# 05_eMMC.net
KiCad netlist of a schematic drawn in Altium Designer
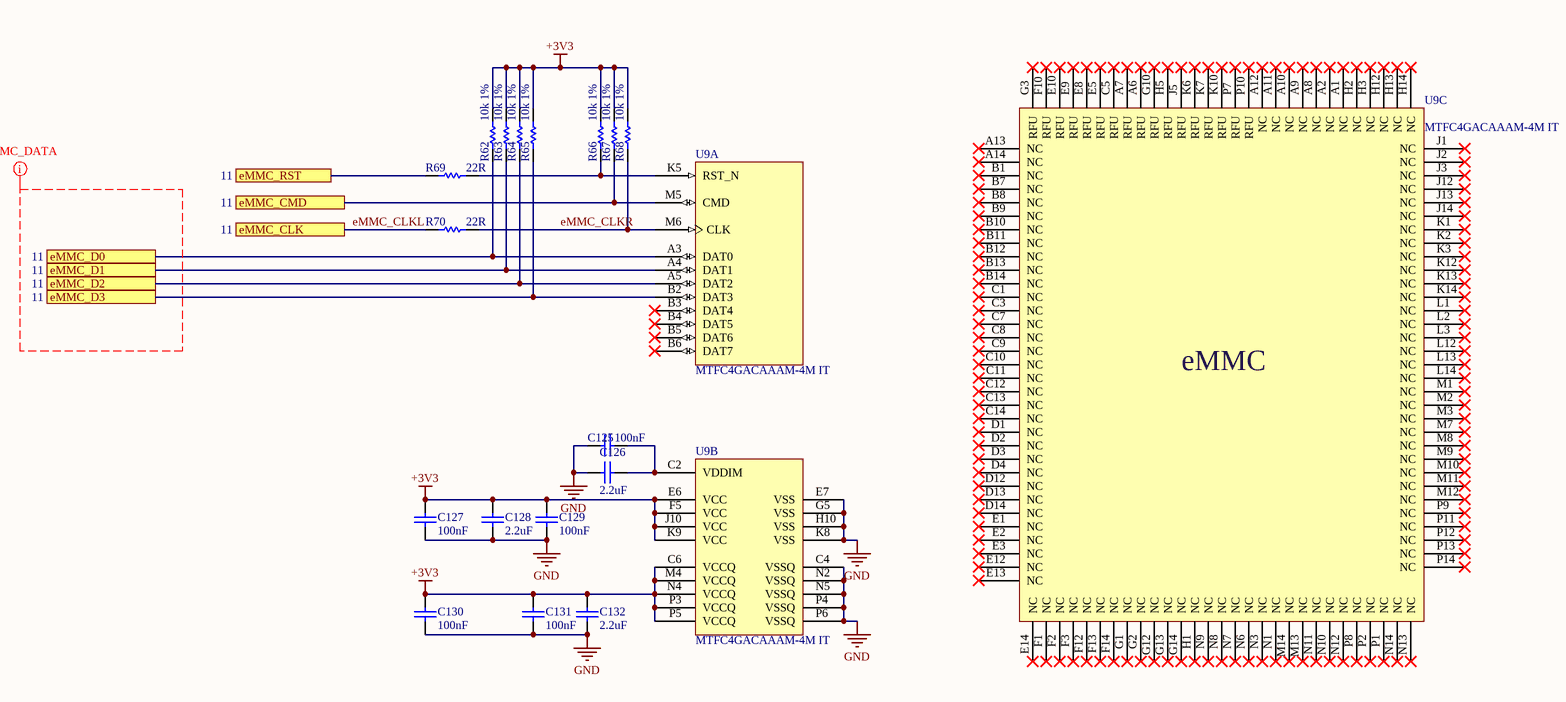
[diagram p0: 05. eMMC.SchDoc]

(export (version "E")
  (design (tool "Eeschema 10.0.6"))
  (components
    (comp (ref "C125")
      (value "100nF")
      (footprint "CAPC1005X60X30LL05T10")
      (description "Chip Capacitor, 0.1 uF, +/- 10%, 16 V, -55 to 125 degC, 0402 (1005 Metric), RoHS, Tape and Reel")
      (fields (field (name "VOLTAGE") "16V") (field (name "TOLERANCE") "10%"))
      (libsource (lib "AM3358_DEV_BOARD") (part "CAP-NP-2"))
    )
    (comp (ref "C126")
      (value "2.2uF")
      (footprint "CAPC1608X90X35ML10T15")
      (description "CAP 2.2uF 10V ±10% 0603 (1608 Metric) Thickness 0.6mm SMD")
      (fields (field (name "MANUFACTURER") "Murata") (field (name "PART NUMBER") "GRM188R71A225KE15D"))
      (libsource (lib "Altium Content Vault") (part "CAP"))
    )
    (comp (ref "C127")
      (value "100nF")
      (footprint "CAPC1005X60X30LL05T10")
      (description "Chip Capacitor, 0.1 uF, +/- 10%, 16 V, -55 to 125 degC, 0402 (1005 Metric), RoHS, Tape and Reel")
      (fields (field (name "VOLTAGE") "16V") (field (name "TOLERANCE") "10%"))
      (libsource (lib "AM3358_DEV_BOARD") (part "CAP-NP-2"))
    )
    (comp (ref "C128")
      (value "2.2uF")
      (footprint "CAPC1005X60X30LL05T10")
      (description "CAP 2.2uF 10V ±10% 0603 (1608 Metric) Thickness 0.6mm SMD")
      (fields (field (name "MANUFACTURER") "Murata") (field (name "PART NUMBER") "GRM188R71A225KE15D"))
      (libsource (lib "AM3358_DEV_BOARD") (part "CAP"))
    )
    (comp (ref "C129")
      (value "100nF")
      (footprint "CAPC1005X60X30LL05T10")
      (description "Chip Capacitor, 0.1 uF, +/- 10%, 16 V, -55 to 125 degC, 0402 (1005 Metric), RoHS, Tape and Reel")
      (fields (field (name "VOLTAGE") "16V") (field (name "TOLERANCE") "10%"))
      (libsource (lib "AM3358_DEV_BOARD") (part "CAP-NP-2"))
    )
    (comp (ref "C130")
      (value "100nF")
      (footprint "CAPC1005X60X30LL05T10")
      (description "Chip Capacitor, 0.1 uF, +/- 10%, 16 V, -55 to 125 degC, 0402 (1005 Metric), RoHS, Tape and Reel")
      (fields (field (name "VOLTAGE") "16V") (field (name "TOLERANCE") "10%"))
      (libsource (lib "AM3358_DEV_BOARD") (part "CAP-NP-2"))
    )
    (comp (ref "C131")
      (value "100nF")
      (footprint "CAPC1005X60X30LL05T10")
      (description "Chip Capacitor, 0.1 uF, +/- 10%, 16 V, -55 to 125 degC, 0402 (1005 Metric), RoHS, Tape and Reel")
      (fields (field (name "VOLTAGE") "16V") (field (name "TOLERANCE") "10%"))
      (libsource (lib "AM3358_DEV_BOARD") (part "CAP-NP-2"))
    )
    (comp (ref "C132")
      (value "2.2uF")
      (footprint "CAPC1608X90X35ML10T15")
      (description "CAP 2.2uF 10V ±10% 0603 (1608 Metric) Thickness 0.6mm SMD")
      (fields (field (name "MANUFACTURER") "Murata") (field (name "PART NUMBER") "GRM188R71A225KE15D"))
      (libsource (lib "Altium Content Vault") (part "CAP"))
    )
    (comp (ref "R62")
      (value "10k 1%")
      (footprint "RESC1005X40X25LL05T05")
      (description "10k 0.063W 1% 0402 (1005 Metric)  SMD")
      (fields (field (name "MANUFACTURER") "Vishay Dale") (field (name "PART NUMBER") "CRCW040210K0FKED"))
      (libsource (lib "AM3358_DEV_BOARD") (part "RES"))
    )
    (comp (ref "R63")
      (value "10k 1%")
      (footprint "RESC1005X40X25LL05T05")
      (description "10k 0.063W 1% 0402 (1005 Metric)  SMD")
      (fields (field (name "MANUFACTURER") "Vishay Dale") (field (name "PART NUMBER") "CRCW040210K0FKED"))
      (libsource (lib "AM3358_DEV_BOARD") (part "RES"))
    )
    (comp (ref "R64")
      (value "10k 1%")
      (footprint "RESC1005X40X25LL05T05")
      (description "10k 0.063W 1% 0402 (1005 Metric)  SMD")
      (fields (field (name "MANUFACTURER") "Vishay Dale") (field (name "PART NUMBER") "CRCW040210K0FKED"))
      (libsource (lib "AM3358_DEV_BOARD") (part "RES"))
    )
    (comp (ref "R65")
      (value "10k 1%")
      (footprint "RESC1005X40X25LL05T05")
      (description "10k 0.063W 1% 0402 (1005 Metric)  SMD")
      (fields (field (name "MANUFACTURER") "Vishay Dale") (field (name "PART NUMBER") "CRCW040210K0FKED"))
      (libsource (lib "AM3358_DEV_BOARD") (part "RES"))
    )
    (comp (ref "R66")
      (value "10k 1%")
      (footprint "RESC1005X40X25LL05T05")
      (description "10k 0.063W 1% 0402 (1005 Metric)  SMD")
      (fields (field (name "MANUFACTURER") "Vishay Dale") (field (name "PART NUMBER") "CRCW040210K0FKED"))
      (libsource (lib "AM3358_DEV_BOARD") (part "RES"))
    )
    (comp (ref "R67")
      (value "10k 1%")
      (footprint "RESC1005X40X25LL05T05")
      (description "10k 0.063W 1% 0402 (1005 Metric)  SMD")
      (fields (field (name "MANUFACTURER") "Vishay Dale") (field (name "PART NUMBER") "CRCW040210K0FKED"))
      (libsource (lib "AM3358_DEV_BOARD") (part "RES"))
    )
    (comp (ref "R68")
      (value "10k 1%")
      (footprint "RESC1005X40X25LL05T05")
      (description "10k 0.063W 1% 0402 (1005 Metric)  SMD")
      (fields (field (name "MANUFACTURER") "Vishay Dale") (field (name "PART NUMBER") "CRCW040210K0FKED"))
      (libsource (lib "AM3358_DEV_BOARD") (part "RES"))
    )
    (comp (ref "R69")
      (value "22R")
      (footprint "RESC1005X40X25LL05T05")
      (description "Chip Resistor, 22 Ohm, +/- 1%, 0.1 W, -55 to 155 degC, 0402 (1005 Metric), RoHS, Tape and Reel")
      (fields (field (name "PARTNUMBER") "ERJ-2RKF22R0X") (field (name "TOLERANCE") "1%"))
      (libsource (lib "AM3358_DEV_BOARD") (part "RES-2"))
    )
    (comp (ref "R70")
      (value "22R")
      (footprint "RESC1005X40X25LL05T05")
      (description "Chip Resistor, 22 Ohm, +/- 1%, 0.1 W, -55 to 155 degC, 0402 (1005 Metric), RoHS, Tape and Reel")
      (fields (field (name "PARTNUMBER") "ERJ-2RKF22R0X") (field (name "TOLERANCE") "1%"))
      (libsource (lib "AM3358_DEV_BOARD") (part "RES-2"))
    )
    (comp (ref "U9")
      (value "MTFC4GACAAAM-4M IT")
      (footprint "VFBGA-153")
      (description "e·MMC Memory, 4 Gb, 2.7 to 3.6 V, -40 to 85 degC, 153-Ball VFBGA, RoHS")
      (fields (field (name "MANUFACTURER") "Micron"))
      (libsource (lib "AM3358_DEV_BOARD") (part "CMP-2000-05234-1"))
    )
  )
  (nets
    (net (code "1") (name "+3V3") (class "Default")
      (node (ref "C127") (pin "2") (pinfunction "2_2") (pintype "passive"))
      (node (ref "C128") (pin "2") (pinfunction "2_2") (pintype "passive"))
      (node (ref "C129") (pin "2") (pinfunction "2_2") (pintype "passive"))
      (node (ref "C130") (pin "2") (pinfunction "2_2") (pintype "passive"))
      (node (ref "C131") (pin "2") (pinfunction "2_2") (pintype "passive"))
      (node (ref "C132") (pin "2") (pinfunction "2_2") (pintype "passive"))
      (node (ref "R62") (pin "2") (pinfunction "2_2") (pintype "passive"))
      (node (ref "R63") (pin "2") (pinfunction "2_2") (pintype "passive"))
      (node (ref "R64") (pin "2") (pinfunction "2_2") (pintype "passive"))
      (node (ref "R65") (pin "2") (pinfunction "2_2") (pintype "passive"))
      (node (ref "R66") (pin "2") (pinfunction "2_2") (pintype "passive"))
      (node (ref "R67") (pin "2") (pinfunction "2_2") (pintype "passive"))
      (node (ref "R68") (pin "2") (pinfunction "2_2") (pintype "passive"))
      (node (ref "U9") (pin "C6") (pinfunction "VCCQ_C6") (pintype "power_in"))
      (node (ref "U9") (pin "E6") (pinfunction "VCC_E6") (pintype "power_in"))
      (node (ref "U9") (pin "F5") (pinfunction "VCC_F5") (pintype "power_in"))
      (node (ref "U9") (pin "J10") (pinfunction "VCC_J10") (pintype "power_in"))
      (node (ref "U9") (pin "K9") (pinfunction "VCC_K9") (pintype "power_in"))
      (node (ref "U9") (pin "M4") (pinfunction "VCCQ_M4") (pintype "power_in"))
      (node (ref "U9") (pin "N4") (pinfunction "VCCQ_N4") (pintype "power_in"))
      (node (ref "U9") (pin "P3") (pinfunction "VCCQ_P3") (pintype "power_in"))
      (node (ref "U9") (pin "P5") (pinfunction "VCCQ_P5") (pintype "power_in"))
    )
    (net (code "2") (name "/eMMC_CLKL") (class "Default")
      (node (ref "R70") (pin "1") (pinfunction "1_1") (pintype "passive"))
    )
    (net (code "3") (name "/eMMC_CLKR") (class "Default")
      (node (ref "R68") (pin "1") (pinfunction "1_1") (pintype "passive"))
      (node (ref "R70") (pin "2") (pinfunction "2_2") (pintype "passive"))
      (node (ref "U9") (pin "M6") (pinfunction "CLK_M6") (pintype "input"))
    )
    (net (code "4") (name "/eMMC_CMD") (class "Default")
      (node (ref "R67") (pin "1") (pinfunction "1_1") (pintype "passive"))
      (node (ref "U9") (pin "M5") (pinfunction "CMD_M5") (pintype "bidirectional"))
    )
    (net (code "5") (name "/eMMC_D0") (class "Default")
      (node (ref "R62") (pin "1") (pinfunction "1_1") (pintype "passive"))
      (node (ref "U9") (pin "A3") (pinfunction "DAT0_A3") (pintype "bidirectional"))
    )
    (net (code "6") (name "/eMMC_D1") (class "Default")
      (node (ref "R63") (pin "1") (pinfunction "1_1") (pintype "passive"))
      (node (ref "U9") (pin "A4") (pinfunction "DAT1_A4") (pintype "bidirectional"))
    )
    (net (code "7") (name "/eMMC_D2") (class "Default")
      (node (ref "R64") (pin "1") (pinfunction "1_1") (pintype "passive"))
      (node (ref "U9") (pin "A5") (pinfunction "DAT2_A5") (pintype "bidirectional"))
    )
    (net (code "8") (name "/eMMC_D3") (class "Default")
      (node (ref "R65") (pin "1") (pinfunction "1_1") (pintype "passive"))
      (node (ref "U9") (pin "B2") (pinfunction "DAT3_B2") (pintype "bidirectional"))
    )
    (net (code "9") (name "/eMMC_RST") (class "Default")
      (node (ref "R69") (pin "1") (pinfunction "1_1") (pintype "passive"))
    )
    (net (code "10") (name "GND") (class "Default")
      (node (ref "C125") (pin "2") (pinfunction "2_2") (pintype "passive"))
      (node (ref "C126") (pin "2") (pinfunction "2_2") (pintype "passive"))
      (node (ref "C127") (pin "1") (pinfunction "1_1") (pintype "passive"))
      (node (ref "C128") (pin "1") (pinfunction "1_1") (pintype "passive"))
      (node (ref "C129") (pin "1") (pinfunction "1_1") (pintype "passive"))
      (node (ref "C130") (pin "1") (pinfunction "1_1") (pintype "passive"))
      (node (ref "C131") (pin "1") (pinfunction "1_1") (pintype "passive"))
      (node (ref "C132") (pin "1") (pinfunction "1_1") (pintype "passive"))
      (node (ref "U9") (pin "C4") (pinfunction "VSSQ_C4") (pintype "power_in"))
      (node (ref "U9") (pin "E7") (pinfunction "VSS_E7") (pintype "power_in"))
      (node (ref "U9") (pin "G5") (pinfunction "VSS_G5") (pintype "power_in"))
      (node (ref "U9") (pin "H10") (pinfunction "VSS_H10") (pintype "power_in"))
      (node (ref "U9") (pin "K8") (pinfunction "VSS_K8") (pintype "power_in"))
      (node (ref "U9") (pin "N2") (pinfunction "VSSQ_N2") (pintype "power_in"))
      (node (ref "U9") (pin "N5") (pinfunction "VSSQ_N5") (pintype "power_in"))
      (node (ref "U9") (pin "P4") (pinfunction "VSSQ_P4") (pintype "power_in"))
      (node (ref "U9") (pin "P6") (pinfunction "VSSQ_P6") (pintype "power_in"))
    )
    (net (code "11") (name "Net-(U9A-RST_N)") (class "Default")
      (node (ref "R66") (pin "1") (pinfunction "1_1") (pintype "passive"))
      (node (ref "R69") (pin "2") (pinfunction "2_2") (pintype "passive"))
      (node (ref "U9") (pin "K5") (pinfunction "RST_N_K5") (pintype "input"))
    )
    (net (code "12") (name "Net-(U9B-VDDIM)") (class "Default")
      (node (ref "C125") (pin "1") (pinfunction "1_1") (pintype "passive"))
      (node (ref "C126") (pin "1") (pinfunction "1_1") (pintype "passive"))
      (node (ref "U9") (pin "C2") (pinfunction "VDDIM_C2") (pintype "power_in"))
    )
    (net (code "13") (name "unconnected-(U9A-DAT4-PadB3)") (class "Default")
      (node (ref "U9") (pin "B3") (pinfunction "DAT4_B3") (pintype "bidirectional+no_connect"))
    )
    (net (code "14") (name "unconnected-(U9A-DAT5-PadB4)") (class "Default")
      (node (ref "U9") (pin "B4") (pinfunction "DAT5_B4") (pintype "bidirectional+no_connect"))
    )
    (net (code "15") (name "unconnected-(U9A-DAT6-PadB5)") (class "Default")
      (node (ref "U9") (pin "B5") (pinfunction "DAT6_B5") (pintype "bidirectional+no_connect"))
    )
    (net (code "16") (name "unconnected-(U9A-DAT7-PadB6)") (class "Default")
      (node (ref "U9") (pin "B6") (pinfunction "DAT7_B6") (pintype "bidirectional+no_connect"))
    )
    (net (code "17") (name "unconnected-(U9C-NC-PadA1)") (class "Default")
      (node (ref "U9") (pin "A1") (pinfunction "NC_A1") (pintype "passive+no_connect"))
    )
    (net (code "18") (name "unconnected-(U9C-NC-PadA2)") (class "Default")
      (node (ref "U9") (pin "A2") (pinfunction "NC_A2") (pintype "passive+no_connect"))
    )
    (net (code "19") (name "unconnected-(U9C-NC-PadA8)") (class "Default")
      (node (ref "U9") (pin "A8") (pinfunction "NC_A8") (pintype "passive+no_connect"))
    )
    (net (code "20") (name "unconnected-(U9C-NC-PadA9)") (class "Default")
      (node (ref "U9") (pin "A9") (pinfunction "NC_A9") (pintype "passive+no_connect"))
    )
    (net (code "21") (name "unconnected-(U9C-NC-PadA10)") (class "Default")
      (node (ref "U9") (pin "A10") (pinfunction "NC_A10") (pintype "passive+no_connect"))
    )
    (net (code "22") (name "unconnected-(U9C-NC-PadA11)") (class "Default")
      (node (ref "U9") (pin "A11") (pinfunction "NC_A11") (pintype "passive+no_connect"))
    )
    (net (code "23") (name "unconnected-(U9C-NC-PadA12)") (class "Default")
      (node (ref "U9") (pin "A12") (pinfunction "NC_A12") (pintype "passive+no_connect"))
    )
    (net (code "24") (name "unconnected-(U9C-NC-PadA13)") (class "Default")
      (node (ref "U9") (pin "A13") (pinfunction "NC_A13") (pintype "passive+no_connect"))
    )
    (net (code "25") (name "unconnected-(U9C-NC-PadA14)") (class "Default")
      (node (ref "U9") (pin "A14") (pinfunction "NC_A14") (pintype "passive+no_connect"))
    )
    (net (code "26") (name "unconnected-(U9C-NC-PadB1)") (class "Default")
      (node (ref "U9") (pin "B1") (pinfunction "NC_B1") (pintype "passive+no_connect"))
    )
    (net (code "27") (name "unconnected-(U9C-NC-PadB7)") (class "Default")
      (node (ref "U9") (pin "B7") (pinfunction "NC_B7") (pintype "passive+no_connect"))
    )
    (net (code "28") (name "unconnected-(U9C-NC-PadB8)") (class "Default")
      (node (ref "U9") (pin "B8") (pinfunction "NC_B8") (pintype "passive+no_connect"))
    )
    (net (code "29") (name "unconnected-(U9C-NC-PadB9)") (class "Default")
      (node (ref "U9") (pin "B9") (pinfunction "NC_B9") (pintype "passive+no_connect"))
    )
    (net (code "30") (name "unconnected-(U9C-NC-PadB10)") (class "Default")
      (node (ref "U9") (pin "B10") (pinfunction "NC_B10") (pintype "passive+no_connect"))
    )
    (net (code "31") (name "unconnected-(U9C-NC-PadB11)") (class "Default")
      (node (ref "U9") (pin "B11") (pinfunction "NC_B11") (pintype "passive+no_connect"))
    )
    (net (code "32") (name "unconnected-(U9C-NC-PadB12)") (class "Default")
      (node (ref "U9") (pin "B12") (pinfunction "NC_B12") (pintype "passive+no_connect"))
    )
    (net (code "33") (name "unconnected-(U9C-NC-PadB13)") (class "Default")
      (node (ref "U9") (pin "B13") (pinfunction "NC_B13") (pintype "passive+no_connect"))
    )
    (net (code "34") (name "unconnected-(U9C-NC-PadB14)") (class "Default")
      (node (ref "U9") (pin "B14") (pinfunction "NC_B14") (pintype "passive+no_connect"))
    )
    (net (code "35") (name "unconnected-(U9C-NC-PadC1)") (class "Default")
      (node (ref "U9") (pin "C1") (pinfunction "NC_C1") (pintype "passive+no_connect"))
    )
    (net (code "36") (name "unconnected-(U9C-NC-PadC3)") (class "Default")
      (node (ref "U9") (pin "C3") (pinfunction "NC_C3") (pintype "passive+no_connect"))
    )
    (net (code "37") (name "unconnected-(U9C-NC-PadC7)") (class "Default")
      (node (ref "U9") (pin "C7") (pinfunction "NC_C7") (pintype "passive+no_connect"))
    )
    (net (code "38") (name "unconnected-(U9C-NC-PadC8)") (class "Default")
      (node (ref "U9") (pin "C8") (pinfunction "NC_C8") (pintype "passive+no_connect"))
    )
    (net (code "39") (name "unconnected-(U9C-NC-PadC9)") (class "Default")
      (node (ref "U9") (pin "C9") (pinfunction "NC_C9") (pintype "passive+no_connect"))
    )
    (net (code "40") (name "unconnected-(U9C-NC-PadC10)") (class "Default")
      (node (ref "U9") (pin "C10") (pinfunction "NC_C10") (pintype "passive+no_connect"))
    )
    (net (code "41") (name "unconnected-(U9C-NC-PadC11)") (class "Default")
      (node (ref "U9") (pin "C11") (pinfunction "NC_C11") (pintype "passive+no_connect"))
    )
    (net (code "42") (name "unconnected-(U9C-NC-PadC12)") (class "Default")
      (node (ref "U9") (pin "C12") (pinfunction "NC_C12") (pintype "passive+no_connect"))
    )
    (net (code "43") (name "unconnected-(U9C-NC-PadC13)") (class "Default")
      (node (ref "U9") (pin "C13") (pinfunction "NC_C13") (pintype "passive+no_connect"))
    )
    (net (code "44") (name "unconnected-(U9C-NC-PadC14)") (class "Default")
      (node (ref "U9") (pin "C14") (pinfunction "NC_C14") (pintype "passive+no_connect"))
    )
    (net (code "45") (name "unconnected-(U9C-NC-PadD1)") (class "Default")
      (node (ref "U9") (pin "D1") (pinfunction "NC_D1") (pintype "passive+no_connect"))
    )
    (net (code "46") (name "unconnected-(U9C-NC-PadD2)") (class "Default")
      (node (ref "U9") (pin "D2") (pinfunction "NC_D2") (pintype "passive+no_connect"))
    )
    (net (code "47") (name "unconnected-(U9C-NC-PadD3)") (class "Default")
      (node (ref "U9") (pin "D3") (pinfunction "NC_D3") (pintype "passive+no_connect"))
    )
    (net (code "48") (name "unconnected-(U9C-NC-PadD4)") (class "Default")
      (node (ref "U9") (pin "D4") (pinfunction "NC_D4") (pintype "passive+no_connect"))
    )
    (net (code "49") (name "unconnected-(U9C-NC-PadD12)") (class "Default")
      (node (ref "U9") (pin "D12") (pinfunction "NC_D12") (pintype "passive+no_connect"))
    )
    (net (code "50") (name "unconnected-(U9C-NC-PadD13)") (class "Default")
      (node (ref "U9") (pin "D13") (pinfunction "NC_D13") (pintype "passive+no_connect"))
    )
    (net (code "51") (name "unconnected-(U9C-NC-PadD14)") (class "Default")
      (node (ref "U9") (pin "D14") (pinfunction "NC_D14") (pintype "passive+no_connect"))
    )
    (net (code "52") (name "unconnected-(U9C-NC-PadE1)") (class "Default")
      (node (ref "U9") (pin "E1") (pinfunction "NC_E1") (pintype "passive+no_connect"))
    )
    (net (code "53") (name "unconnected-(U9C-NC-PadE2)") (class "Default")
      (node (ref "U9") (pin "E2") (pinfunction "NC_E2") (pintype "passive+no_connect"))
    )
    (net (code "54") (name "unconnected-(U9C-NC-PadE3)") (class "Default")
      (node (ref "U9") (pin "E3") (pinfunction "NC_E3") (pintype "passive+no_connect"))
    )
    (net (code "55") (name "unconnected-(U9C-NC-PadE12)") (class "Default")
      (node (ref "U9") (pin "E12") (pinfunction "NC_E12") (pintype "passive+no_connect"))
    )
    (net (code "56") (name "unconnected-(U9C-NC-PadE13)") (class "Default")
      (node (ref "U9") (pin "E13") (pinfunction "NC_E13") (pintype "passive+no_connect"))
    )
    (net (code "57") (name "unconnected-(U9C-NC-PadE14)") (class "Default")
      (node (ref "U9") (pin "E14") (pinfunction "NC_E14") (pintype "passive+no_connect"))
    )
    (net (code "58") (name "unconnected-(U9C-NC-PadF1)") (class "Default")
      (node (ref "U9") (pin "F1") (pinfunction "NC_F1") (pintype "passive+no_connect"))
    )
    (net (code "59") (name "unconnected-(U9C-NC-PadF2)") (class "Default")
      (node (ref "U9") (pin "F2") (pinfunction "NC_F2") (pintype "passive+no_connect"))
    )
    (net (code "60") (name "unconnected-(U9C-NC-PadF3)") (class "Default")
      (node (ref "U9") (pin "F3") (pinfunction "NC_F3") (pintype "passive+no_connect"))
    )
    (net (code "61") (name "unconnected-(U9C-NC-PadF12)") (class "Default")
      (node (ref "U9") (pin "F12") (pinfunction "NC_F12") (pintype "passive+no_connect"))
    )
    (net (code "62") (name "unconnected-(U9C-NC-PadF13)") (class "Default")
      (node (ref "U9") (pin "F13") (pinfunction "NC_F13") (pintype "passive+no_connect"))
    )
    (net (code "63") (name "unconnected-(U9C-NC-PadF14)") (class "Default")
      (node (ref "U9") (pin "F14") (pinfunction "NC_F14") (pintype "passive+no_connect"))
    )
    (net (code "64") (name "unconnected-(U9C-NC-PadG1)") (class "Default")
      (node (ref "U9") (pin "G1") (pinfunction "NC_G1") (pintype "passive+no_connect"))
    )
    (net (code "65") (name "unconnected-(U9C-NC-PadG2)") (class "Default")
      (node (ref "U9") (pin "G2") (pinfunction "NC_G2") (pintype "passive+no_connect"))
    )
    (net (code "66") (name "unconnected-(U9C-NC-PadG12)") (class "Default")
      (node (ref "U9") (pin "G12") (pinfunction "NC_G12") (pintype "passive+no_connect"))
    )
    (net (code "67") (name "unconnected-(U9C-NC-PadG13)") (class "Default")
      (node (ref "U9") (pin "G13") (pinfunction "NC_G13") (pintype "passive+no_connect"))
    )
    (net (code "68") (name "unconnected-(U9C-NC-PadG14)") (class "Default")
      (node (ref "U9") (pin "G14") (pinfunction "NC_G14") (pintype "passive+no_connect"))
    )
    (net (code "69") (name "unconnected-(U9C-NC-PadH1)") (class "Default")
      (node (ref "U9") (pin "H1") (pinfunction "NC_H1") (pintype "passive+no_connect"))
    )
    (net (code "70") (name "unconnected-(U9C-NC-PadH2)") (class "Default")
      (node (ref "U9") (pin "H2") (pinfunction "NC_H2") (pintype "passive+no_connect"))
    )
    (net (code "71") (name "unconnected-(U9C-NC-PadH3)") (class "Default")
      (node (ref "U9") (pin "H3") (pinfunction "NC_H3") (pintype "passive+no_connect"))
    )
    (net (code "72") (name "unconnected-(U9C-NC-PadH12)") (class "Default")
      (node (ref "U9") (pin "H12") (pinfunction "NC_H12") (pintype "passive+no_connect"))
    )
    (net (code "73") (name "unconnected-(U9C-NC-PadH13)") (class "Default")
      (node (ref "U9") (pin "H13") (pinfunction "NC_H13") (pintype "passive+no_connect"))
    )
    (net (code "74") (name "unconnected-(U9C-NC-PadH14)") (class "Default")
      (node (ref "U9") (pin "H14") (pinfunction "NC_H14") (pintype "passive+no_connect"))
    )
    (net (code "75") (name "unconnected-(U9C-NC-PadJ1)") (class "Default")
      (node (ref "U9") (pin "J1") (pinfunction "NC_J1") (pintype "passive+no_connect"))
    )
    (net (code "76") (name "unconnected-(U9C-NC-PadJ2)") (class "Default")
      (node (ref "U9") (pin "J2") (pinfunction "NC_J2") (pintype "passive+no_connect"))
    )
    (net (code "77") (name "unconnected-(U9C-NC-PadJ3)") (class "Default")
      (node (ref "U9") (pin "J3") (pinfunction "NC_J3") (pintype "passive+no_connect"))
    )
    (net (code "78") (name "unconnected-(U9C-NC-PadJ12)") (class "Default")
      (node (ref "U9") (pin "J12") (pinfunction "NC_J12") (pintype "passive+no_connect"))
    )
    (net (code "79") (name "unconnected-(U9C-NC-PadJ13)") (class "Default")
      (node (ref "U9") (pin "J13") (pinfunction "NC_J13") (pintype "passive+no_connect"))
    )
    (net (code "80") (name "unconnected-(U9C-NC-PadJ14)") (class "Default")
      (node (ref "U9") (pin "J14") (pinfunction "NC_J14") (pintype "passive+no_connect"))
    )
    (net (code "81") (name "unconnected-(U9C-NC-PadK1)") (class "Default")
      (node (ref "U9") (pin "K1") (pinfunction "NC_K1") (pintype "passive+no_connect"))
    )
    (net (code "82") (name "unconnected-(U9C-NC-PadK2)") (class "Default")
      (node (ref "U9") (pin "K2") (pinfunction "NC_K2") (pintype "passive+no_connect"))
    )
    (net (code "83") (name "unconnected-(U9C-NC-PadK3)") (class "Default")
      (node (ref "U9") (pin "K3") (pinfunction "NC_K3") (pintype "passive+no_connect"))
    )
    (net (code "84") (name "unconnected-(U9C-NC-PadK12)") (class "Default")
      (node (ref "U9") (pin "K12") (pinfunction "NC_K12") (pintype "passive+no_connect"))
    )
    (net (code "85") (name "unconnected-(U9C-NC-PadK13)") (class "Default")
      (node (ref "U9") (pin "K13") (pinfunction "NC_K13") (pintype "passive+no_connect"))
    )
    (net (code "86") (name "unconnected-(U9C-NC-PadK14)") (class "Default")
      (node (ref "U9") (pin "K14") (pinfunction "NC_K14") (pintype "passive+no_connect"))
    )
    (net (code "87") (name "unconnected-(U9C-NC-PadL1)") (class "Default")
      (node (ref "U9") (pin "L1") (pinfunction "NC_L1") (pintype "passive+no_connect"))
    )
    (net (code "88") (name "unconnected-(U9C-NC-PadL2)") (class "Default")
      (node (ref "U9") (pin "L2") (pinfunction "NC_L2") (pintype "passive+no_connect"))
    )
    (net (code "89") (name "unconnected-(U9C-NC-PadL3)") (class "Default")
      (node (ref "U9") (pin "L3") (pinfunction "NC_L3") (pintype "passive+no_connect"))
    )
    (net (code "90") (name "unconnected-(U9C-NC-PadL12)") (class "Default")
      (node (ref "U9") (pin "L12") (pinfunction "NC_L12") (pintype "passive+no_connect"))
    )
    (net (code "91") (name "unconnected-(U9C-NC-PadL13)") (class "Default")
      (node (ref "U9") (pin "L13") (pinfunction "NC_L13") (pintype "passive+no_connect"))
    )
    (net (code "92") (name "unconnected-(U9C-NC-PadL14)") (class "Default")
      (node (ref "U9") (pin "L14") (pinfunction "NC_L14") (pintype "passive+no_connect"))
    )
    (net (code "93") (name "unconnected-(U9C-NC-PadM1)") (class "Default")
      (node (ref "U9") (pin "M1") (pinfunction "NC_M1") (pintype "passive+no_connect"))
    )
    (net (code "94") (name "unconnected-(U9C-NC-PadM2)") (class "Default")
      (node (ref "U9") (pin "M2") (pinfunction "NC_M2") (pintype "passive+no_connect"))
    )
    (net (code "95") (name "unconnected-(U9C-NC-PadM3)") (class "Default")
      (node (ref "U9") (pin "M3") (pinfunction "NC_M3") (pintype "passive+no_connect"))
    )
    (net (code "96") (name "unconnected-(U9C-NC-PadM7)") (class "Default")
      (node (ref "U9") (pin "M7") (pinfunction "NC_M7") (pintype "passive+no_connect"))
    )
    (net (code "97") (name "unconnected-(U9C-NC-PadM8)") (class "Default")
      (node (ref "U9") (pin "M8") (pinfunction "NC_M8") (pintype "passive+no_connect"))
    )
    (net (code "98") (name "unconnected-(U9C-NC-PadM9)") (class "Default")
      (node (ref "U9") (pin "M9") (pinfunction "NC_M9") (pintype "passive+no_connect"))
    )
    (net (code "99") (name "unconnected-(U9C-NC-PadM10)") (class "Default")
      (node (ref "U9") (pin "M10") (pinfunction "NC_M10") (pintype "passive+no_connect"))
    )
    (net (code "100") (name "unconnected-(U9C-NC-PadM11)") (class "Default")
      (node (ref "U9") (pin "M11") (pinfunction "NC_M11") (pintype "passive+no_connect"))
    )
    (net (code "101") (name "unconnected-(U9C-NC-PadM12)") (class "Default")
      (node (ref "U9") (pin "M12") (pinfunction "NC_M12") (pintype "passive+no_connect"))
    )
    (net (code "102") (name "unconnected-(U9C-NC-PadM13)") (class "Default")
      (node (ref "U9") (pin "M13") (pinfunction "NC_M13") (pintype "passive+no_connect"))
    )
    (net (code "103") (name "unconnected-(U9C-NC-PadM14)") (class "Default")
      (node (ref "U9") (pin "M14") (pinfunction "NC_M14") (pintype "passive+no_connect"))
    )
    (net (code "104") (name "unconnected-(U9C-NC-PadN1)") (class "Default")
      (node (ref "U9") (pin "N1") (pinfunction "NC_N1") (pintype "passive+no_connect"))
    )
    (net (code "105") (name "unconnected-(U9C-NC-PadN3)") (class "Default")
      (node (ref "U9") (pin "N3") (pinfunction "NC_N3") (pintype "passive+no_connect"))
    )
    (net (code "106") (name "unconnected-(U9C-NC-PadN6)") (class "Default")
      (node (ref "U9") (pin "N6") (pinfunction "NC_N6") (pintype "passive+no_connect"))
    )
    (net (code "107") (name "unconnected-(U9C-NC-PadN7)") (class "Default")
      (node (ref "U9") (pin "N7") (pinfunction "NC_N7") (pintype "passive+no_connect"))
    )
    (net (code "108") (name "unconnected-(U9C-NC-PadN8)") (class "Default")
      (node (ref "U9") (pin "N8") (pinfunction "NC_N8") (pintype "passive+no_connect"))
    )
    (net (code "109") (name "unconnected-(U9C-NC-PadN9)") (class "Default")
      (node (ref "U9") (pin "N9") (pinfunction "NC_N9") (pintype "passive+no_connect"))
    )
    (net (code "110") (name "unconnected-(U9C-NC-PadN10)") (class "Default")
      (node (ref "U9") (pin "N10") (pinfunction "NC_N10") (pintype "passive+no_connect"))
    )
    (net (code "111") (name "unconnected-(U9C-NC-PadN11)") (class "Default")
      (node (ref "U9") (pin "N11") (pinfunction "NC_N11") (pintype "passive+no_connect"))
    )
    (net (code "112") (name "unconnected-(U9C-NC-PadN12)") (class "Default")
      (node (ref "U9") (pin "N12") (pinfunction "NC_N12") (pintype "passive+no_connect"))
    )
    (net (code "113") (name "unconnected-(U9C-NC-PadN13)") (class "Default")
      (node (ref "U9") (pin "N13") (pinfunction "NC_N13") (pintype "passive+no_connect"))
    )
    (net (code "114") (name "unconnected-(U9C-NC-PadN14)") (class "Default")
      (node (ref "U9") (pin "N14") (pinfunction "NC_N14") (pintype "passive+no_connect"))
    )
    (net (code "115") (name "unconnected-(U9C-NC-PadP1)") (class "Default")
      (node (ref "U9") (pin "P1") (pinfunction "NC_P1") (pintype "passive+no_connect"))
    )
    (net (code "116") (name "unconnected-(U9C-NC-PadP2)") (class "Default")
      (node (ref "U9") (pin "P2") (pinfunction "NC_P2") (pintype "passive+no_connect"))
    )
    (net (code "117") (name "unconnected-(U9C-NC-PadP8)") (class "Default")
      (node (ref "U9") (pin "P8") (pinfunction "NC_P8") (pintype "passive+no_connect"))
    )
    (net (code "118") (name "unconnected-(U9C-NC-PadP9)") (class "Default")
      (node (ref "U9") (pin "P9") (pinfunction "NC_P9") (pintype "passive+no_connect"))
    )
    (net (code "119") (name "unconnected-(U9C-NC-PadP11)") (class "Default")
      (node (ref "U9") (pin "P11") (pinfunction "NC_P11") (pintype "passive+no_connect"))
    )
    (net (code "120") (name "unconnected-(U9C-NC-PadP12)") (class "Default")
      (node (ref "U9") (pin "P12") (pinfunction "NC_P12") (pintype "passive+no_connect"))
    )
    (net (code "121") (name "unconnected-(U9C-NC-PadP13)") (class "Default")
      (node (ref "U9") (pin "P13") (pinfunction "NC_P13") (pintype "passive+no_connect"))
    )
    (net (code "122") (name "unconnected-(U9C-NC-PadP14)") (class "Default")
      (node (ref "U9") (pin "P14") (pinfunction "NC_P14") (pintype "passive+no_connect"))
    )
    (net (code "123") (name "unconnected-(U9C-RFU-PadA6)") (class "Default")
      (node (ref "U9") (pin "A6") (pinfunction "RFU_A6") (pintype "passive+no_connect"))
    )
    (net (code "124") (name "unconnected-(U9C-RFU-PadA7)") (class "Default")
      (node (ref "U9") (pin "A7") (pinfunction "RFU_A7") (pintype "passive+no_connect"))
    )
    (net (code "125") (name "unconnected-(U9C-RFU-PadC5)") (class "Default")
      (node (ref "U9") (pin "C5") (pinfunction "RFU_C5") (pintype "passive+no_connect"))
    )
    (net (code "126") (name "unconnected-(U9C-RFU-PadE5)") (class "Default")
      (node (ref "U9") (pin "E5") (pinfunction "RFU_E5") (pintype "passive+no_connect"))
    )
    (net (code "127") (name "unconnected-(U9C-RFU-PadE8)") (class "Default")
      (node (ref "U9") (pin "E8") (pinfunction "RFU_E8") (pintype "passive+no_connect"))
    )
    (net (code "128") (name "unconnected-(U9C-RFU-PadE9)") (class "Default")
      (node (ref "U9") (pin "E9") (pinfunction "RFU_E9") (pintype "passive+no_connect"))
    )
    (net (code "129") (name "unconnected-(U9C-RFU-PadE10)") (class "Default")
      (node (ref "U9") (pin "E10") (pinfunction "RFU_E10") (pintype "passive+no_connect"))
    )
    (net (code "130") (name "unconnected-(U9C-RFU-PadF10)") (class "Default")
      (node (ref "U9") (pin "F10") (pinfunction "RFU_F10") (pintype "passive+no_connect"))
    )
    (net (code "131") (name "unconnected-(U9C-RFU-PadG3)") (class "Default")
      (node (ref "U9") (pin "G3") (pinfunction "RFU_G3") (pintype "passive+no_connect"))
    )
    (net (code "132") (name "unconnected-(U9C-RFU-PadG10)") (class "Default")
      (node (ref "U9") (pin "G10") (pinfunction "RFU_G10") (pintype "passive+no_connect"))
    )
    (net (code "133") (name "unconnected-(U9C-RFU-PadH5)") (class "Default")
      (node (ref "U9") (pin "H5") (pinfunction "RFU_H5") (pintype "passive+no_connect"))
    )
    (net (code "134") (name "unconnected-(U9C-RFU-PadJ5)") (class "Default")
      (node (ref "U9") (pin "J5") (pinfunction "RFU_J5") (pintype "passive+no_connect"))
    )
    (net (code "135") (name "unconnected-(U9C-RFU-PadK6)") (class "Default")
      (node (ref "U9") (pin "K6") (pinfunction "RFU_K6") (pintype "passive+no_connect"))
    )
    (net (code "136") (name "unconnected-(U9C-RFU-PadK7)") (class "Default")
      (node (ref "U9") (pin "K7") (pinfunction "RFU_K7") (pintype "passive+no_connect"))
    )
    (net (code "137") (name "unconnected-(U9C-RFU-PadK10)") (class "Default")
      (node (ref "U9") (pin "K10") (pinfunction "RFU_K10") (pintype "passive+no_connect"))
    )
    (net (code "138") (name "unconnected-(U9C-RFU-PadP7)") (class "Default")
      (node (ref "U9") (pin "P7") (pinfunction "RFU_P7") (pintype "passive+no_connect"))
    )
    (net (code "139") (name "unconnected-(U9C-RFU-PadP10)") (class "Default")
      (node (ref "U9") (pin "P10") (pinfunction "RFU_P10") (pintype "passive+no_connect"))
    )
  )
)
